# Oxport_Project.net
KiCad netlist of a schematic drawn in EAGLE
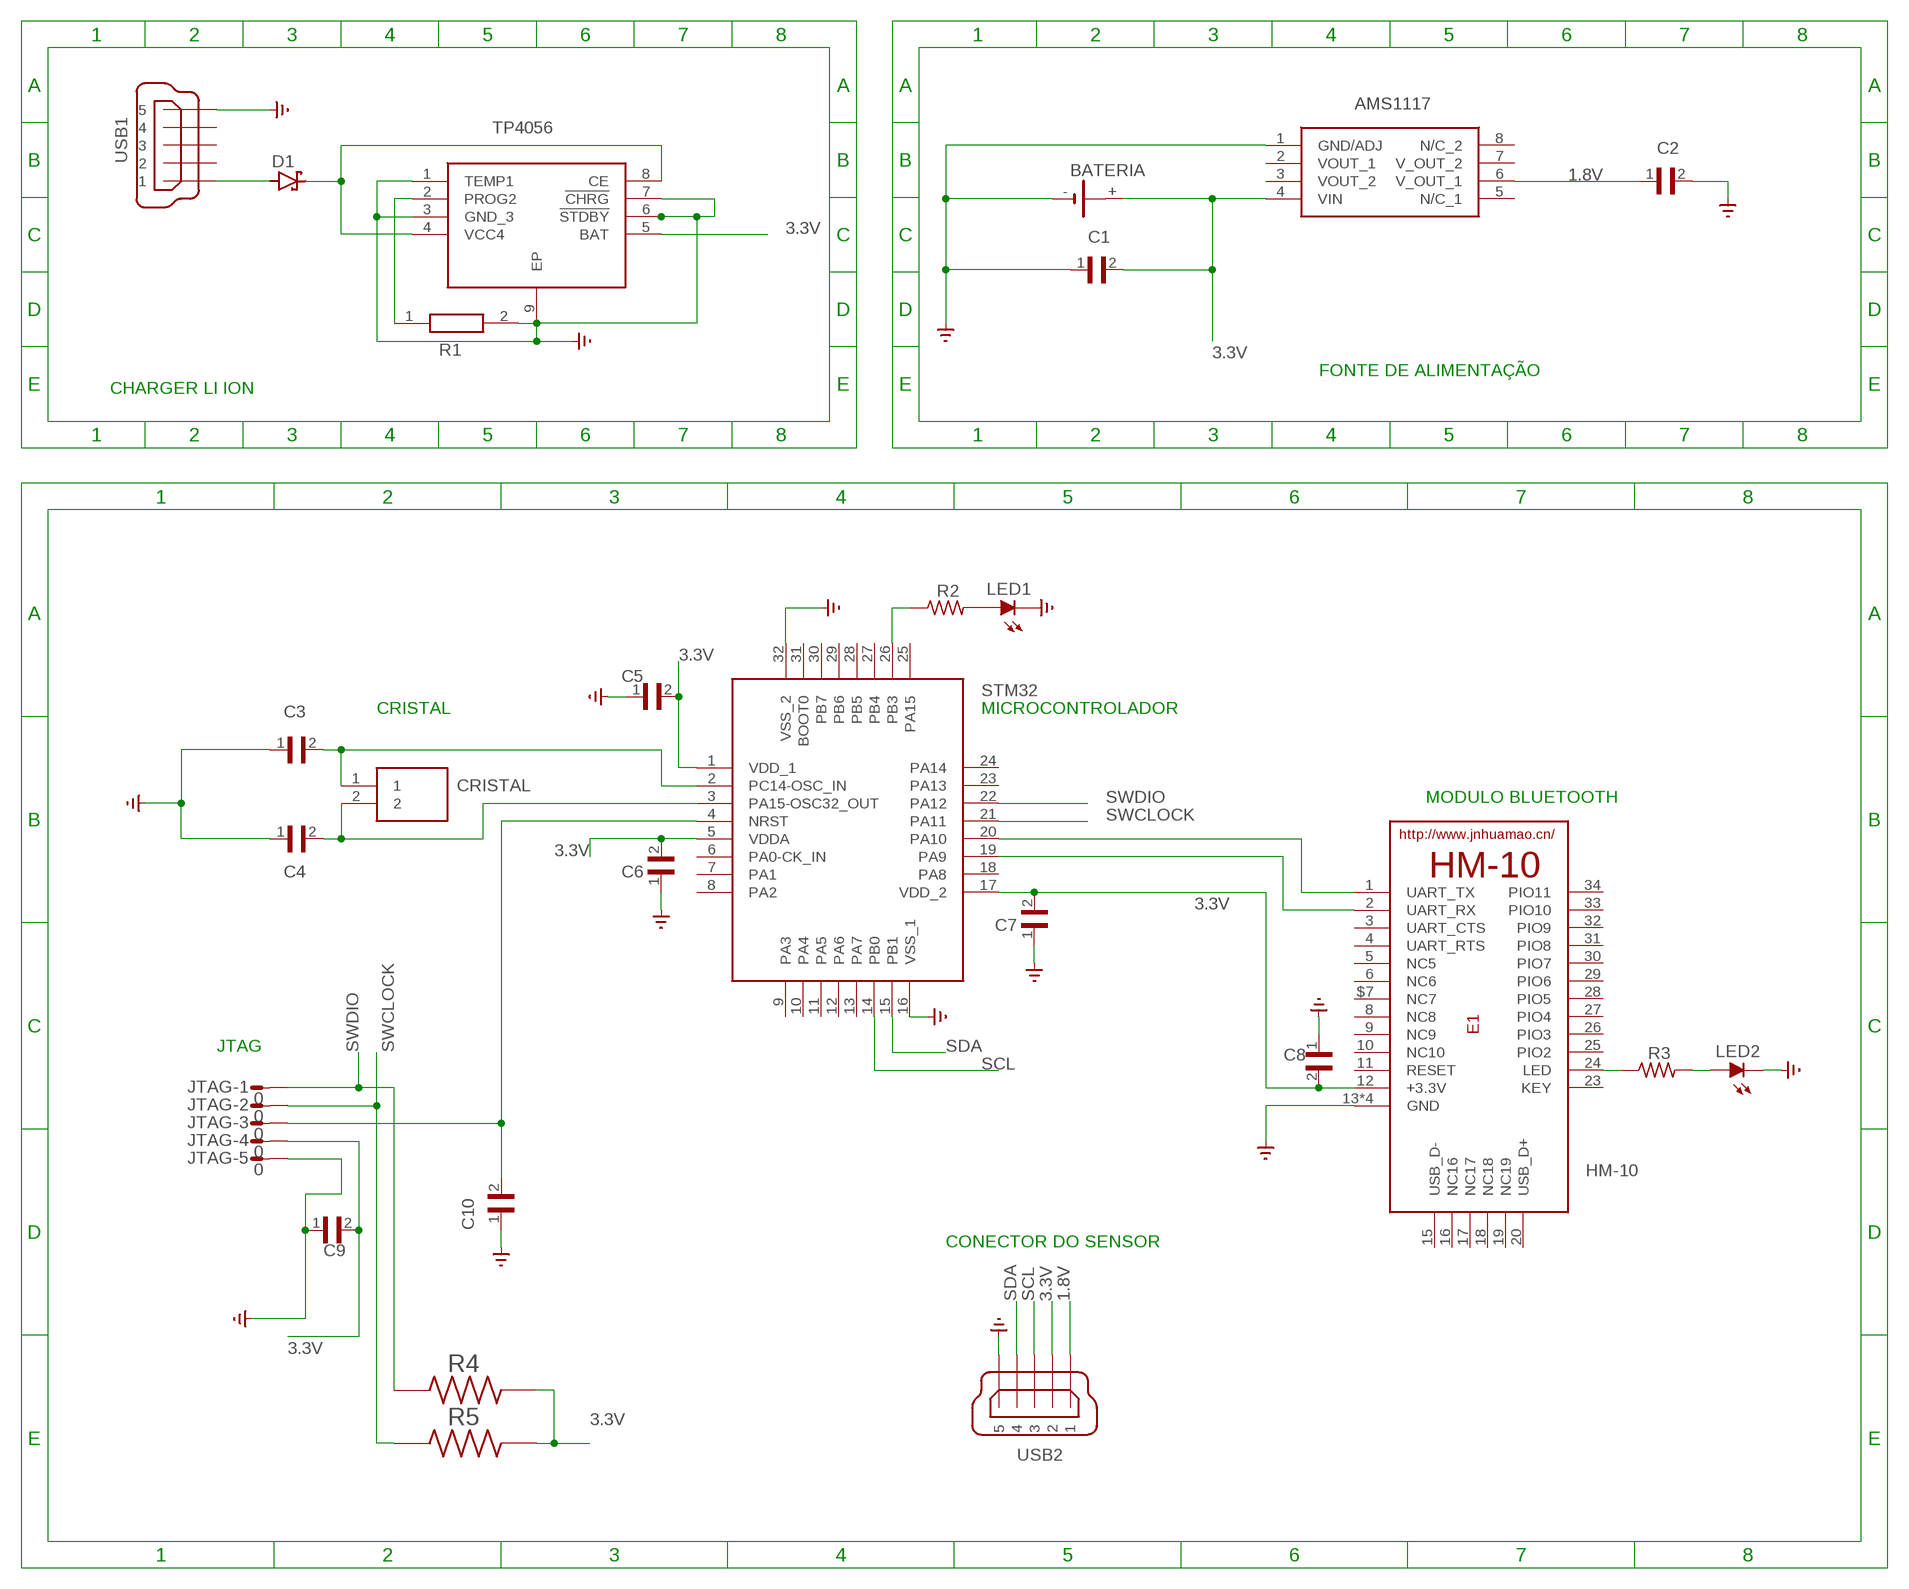
[diagram p0: schematic, sheet 1]

(export (version "E")
  (design (tool "Eeschema 10.0.6"))
  (components
    (comp (ref "3.3V")
      (value "STM32L031K6T6TR")
      (footprint "eagle-import:QFP80P900X900X160-32N")
      (fields (field (name "MOUSER_PART_NUMBER") "511-STM32L031K6T6TR"))
      (libsource (lib "eagle-import") (part "STM32L031K6T6TR"))
    )
    (comp (ref "BATERIA")
      (value "CR1/2")
      (footprint "eagle-import:CR1_2")
      (libsource (lib "eagle-import") (part "CR1/2"))
    )
    (comp (ref "C1")
      (value "VJ0603Y104KLXAC5G")
      (footprint "eagle-import:CAPC1608X92N")
      (fields (field (name "MF") "Vishay"))
      (libsource (lib "eagle-import") (part "VJ0603Y104KLXAC5G"))
    )
    (comp (ref "C2")
      (value "VJ0603Y104KLXAC5G")
      (footprint "eagle-import:CAPC1608X92N")
      (fields (field (name "MF") "Vishay"))
      (libsource (lib "eagle-import") (part "VJ0603Y104KLXAC5G"))
    )
    (comp (ref "C3")
      (value "GRM1885C2A4R3CZ01D")
      (footprint "eagle-import:CAPC1608X90N")
      (fields (field (name "MF") "Murata"))
      (libsource (lib "eagle-import") (part "GRM1885C2A4R3CZ01D"))
    )
    (comp (ref "C4")
      (value "GRM1885C2A4R3CZ01D")
      (footprint "eagle-import:CAPC1608X90N")
      (fields (field (name "MF") "Murata"))
      (libsource (lib "eagle-import") (part "GRM1885C2A4R3CZ01D"))
    )
    (comp (ref "C5")
      (value "VJ0603Y104KLXAC5G")
      (footprint "eagle-import:CAPC1608X92N")
      (fields (field (name "MF") "Vishay"))
      (libsource (lib "eagle-import") (part "VJ0603Y104KLXAC5G"))
    )
    (comp (ref "C6")
      (value "VJ0603Y104KLXAC5G")
      (footprint "eagle-import:CAPC1608X92N")
      (fields (field (name "MF") "Vishay"))
      (libsource (lib "eagle-import") (part "VJ0603Y104KLXAC5G"))
    )
    (comp (ref "C7")
      (value "VJ0603Y104KLXAC5G")
      (footprint "eagle-import:CAPC1608X92N")
      (fields (field (name "MF") "Vishay"))
      (libsource (lib "eagle-import") (part "VJ0603Y104KLXAC5G"))
    )
    (comp (ref "C8")
      (value "VJ0603Y104KLXAC5G")
      (footprint "eagle-import:CAPC1608X92N")
      (fields (field (name "MF") "Vishay"))
      (libsource (lib "eagle-import") (part "VJ0603Y104KLXAC5G"))
    )
    (comp (ref "C9")
      (value "VJ0603Y104KLXAC5G")
      (footprint "eagle-import:CAPC1608X92N")
      (fields (field (name "MF") "Vishay"))
      (libsource (lib "eagle-import") (part "VJ0603Y104KLXAC5G"))
    )
    (comp (ref "C10")
      (value "VJ0603Y104KLXAC5G")
      (footprint "eagle-import:CAPC1608X92N")
      (fields (field (name "MF") "Vishay"))
      (libsource (lib "eagle-import") (part "VJ0603Y104KLXAC5G"))
    )
    (comp (ref "CRISTAL")
      (value "NX3215SA-32.768K-EXS00A-MU0000")
      (footprint "eagle-import:NX3215SA32768KEXS00AMU00003")
      (fields
        (field (name "MANUFACTURER_PART_NUMBER") "NX3215SA-32.768K-EXS00A-MU00003")
        (field (name "MOUSER_PART_NUMBER") "344-NX3215SA32.768K3")
      )
      (libsource (lib "eagle-import") (part "NX3215SA-32.768K-EXS00A-MU0000"))
    )
    (comp (ref "D1")
      (value "BAT60J")
      (footprint "eagle-import:SOD323_ST")
      (libsource (lib "eagle-import") (part "BAT60J"))
    )
    (comp (ref "E1")
      (value "HM-10-BOARD")
      (footprint "eagle-import:26.9X13X2.2_BOARD")
      (libsource (lib "eagle-import") (part "HM-10-BOARD"))
    )
    (comp (ref "IC2")
      (value "AMS1117CS-1.8")
      (footprint "eagle-import:SOIC127P599X175-8N")
      (libsource (lib "eagle-import") (part "AMS1117CS-1.8"))
    )
    (comp (ref "J1")
      (value "TP4056")
      (footprint "eagle-import:SOIC127P600X175-9N")
      (libsource (lib "eagle-import") (part "TP4056"))
    )
    (comp (ref "JTAG")
      (value "0")
      (footprint "eagle-import:L05P")
      (libsource (lib "eagle-import") (part "L05P"))
    )
    (comp (ref "LED1")
      (value "1")
      (footprint "eagle-import:LED_CHIP-LED0603MP")
      (libsource (lib "eagle-import") (part "LED_LEDCHIP-LED0603MP"))
    )
    (comp (ref "LED2")
      (value "1")
      (footprint "eagle-import:LED_CHIP-LED0603MP")
      (libsource (lib "eagle-import") (part "LED_LEDCHIP-LED0603MP"))
    )
    (comp (ref "MINI_USB")
      (value "MINI-USB_SHIELD5P4-32005-501")
      (footprint "eagle-import:32005-501")
      (libsource (lib "eagle-import") (part "MINI-USB_SHIELD5P4-32005-501"))
    )
    (comp (ref "R1")
      (value "CRCW08051K00FKEB")
      (footprint "eagle-import:RESC2012X50N")
      (fields (field (name "MOUSER_PART_NUMBER") "71-CRCW08051K00FKEB"))
      (libsource (lib "eagle-import") (part "CRCW08051K00FKEB"))
    )
    (comp (ref "R2")
      (value "1623232-1")
      (footprint "eagle-import:RESC2012X65N")
      (fields (field (name "MF") "TE Connectivity") (field (name "TOLERANCE") "1%"))
      (libsource (lib "eagle-import") (part "1623232-1"))
    )
    (comp (ref "R3")
      (value "1623232-1")
      (footprint "eagle-import:RESC2012X65N")
      (fields (field (name "MF") "TE Connectivity") (field (name "TOLERANCE") "1%"))
      (libsource (lib "eagle-import") (part "1623232-1"))
    )
    (comp (ref "R4")
      (value "CRGCQ1206J10K")
      (footprint "eagle-import:RESC3115X65N")
      (fields (field (name "COMMENT") "2-2176344-5") (field (name "MF") "TE Connectivity"))
      (libsource (lib "eagle-import") (part "CRGCQ1206J10K"))
    )
    (comp (ref "R5")
      (value "CRGCQ1206J10K")
      (footprint "eagle-import:RESC3115X65N")
      (fields (field (name "COMMENT") "2-2176344-5") (field (name "MF") "TE Connectivity"))
      (libsource (lib "eagle-import") (part "CRGCQ1206J10K"))
    )
    (comp (ref "USB1")
      (value "MINI-USB_SHIELD5P4-32005-501")
      (footprint "eagle-import:32005-501")
      (libsource (lib "eagle-import") (part "MINI-USB_SHIELD5P4-32005-501"))
    )
  )
  (nets
    (net (code "1") (name "/1.8V") (class "Default")
      (node (ref "C2") (pin "1") (pinfunction "1_1") (pintype "passive"))
      (node (ref "IC2") (pin "6") (pinfunction "V_OUT_1_6") (pintype "bidirectional"))
      (node (ref "USB1") (pin "1") (pinfunction "1_1") (pintype "passive"))
    )
    (net (code "2") (name "/3.3V") (class "Default")
      (node (ref "3.3V") (pin "1") (pinfunction "VDD_1_1") (pintype "bidirectional"))
      (node (ref "3.3V") (pin "17") (pinfunction "VDD_2_17") (pintype "bidirectional"))
      (node (ref "3.3V") (pin "5") (pinfunction "VDDA_5") (pintype "bidirectional"))
      (node (ref "BATERIA") (pin "+") (pinfunction "+_+") (pintype "passive"))
      (node (ref "C1") (pin "2") (pinfunction "2_2") (pintype "passive"))
      (node (ref "C5") (pin "2") (pinfunction "2_2") (pintype "passive"))
      (node (ref "C6") (pin "2") (pinfunction "2_2") (pintype "passive"))
      (node (ref "C7") (pin "2") (pinfunction "2_2") (pintype "passive"))
      (node (ref "C8") (pin "2") (pinfunction "2_2") (pintype "passive"))
      (node (ref "C9") (pin "2") (pinfunction "2_2") (pintype "passive"))
      (node (ref "E1") (pin "12") (pinfunction "+3.3V_12") (pintype "bidirectional"))
      (node (ref "IC2") (pin "4") (pinfunction "VIN_4") (pintype "bidirectional"))
      (node (ref "J1") (pin "5") (pinfunction "BAT_5") (pintype "bidirectional"))
      (node (ref "JTAG") (pin "4") (pinfunction "S_4") (pintype "passive"))
      (node (ref "R4") (pin "2") (pinfunction "2_2") (pintype "passive"))
      (node (ref "R5") (pin "2") (pinfunction "2_2") (pintype "passive"))
      (node (ref "USB1") (pin "2") (pinfunction "2_2") (pintype "passive"))
    )
    (net (code "3") (name "/SCL") (class "Default")
      (node (ref "3.3V") (pin "14") (pinfunction "PB0_14") (pintype "bidirectional"))
      (node (ref "USB1") (pin "3") (pinfunction "3_3") (pintype "passive"))
    )
    (net (code "4") (name "/SDA") (class "Default")
      (node (ref "3.3V") (pin "15") (pinfunction "PB1_15") (pintype "bidirectional"))
      (node (ref "USB1") (pin "4") (pinfunction "4_4") (pintype "passive"))
    )
    (net (code "5") (name "/SWCLOCK") (class "Default")
      (node (ref "3.3V") (pin "21") (pinfunction "PA11_21") (pintype "bidirectional"))
      (node (ref "JTAG") (pin "2") (pinfunction "S_2") (pintype "passive"))
      (node (ref "R5") (pin "1") (pinfunction "1_1") (pintype "passive"))
    )
    (net (code "6") (name "/SWDIO") (class "Default")
      (node (ref "3.3V") (pin "22") (pinfunction "PA12_22") (pintype "bidirectional"))
      (node (ref "JTAG") (pin "1") (pinfunction "S_1") (pintype "passive"))
      (node (ref "R4") (pin "1") (pinfunction "1_1") (pintype "passive"))
    )
    (net (code "7") (name "Net-(3.3V-NRST)") (class "Default")
      (node (ref "3.3V") (pin "4") (pinfunction "NRST_4") (pintype "bidirectional"))
      (node (ref "C10") (pin "2") (pinfunction "2_2") (pintype "passive"))
      (node (ref "JTAG") (pin "3") (pinfunction "S_3") (pintype "passive"))
    )
    (net (code "8") (name "Net-(3.3V-PA9)") (class "Default")
      (node (ref "3.3V") (pin "19") (pinfunction "PA9_19") (pintype "bidirectional"))
      (node (ref "E1") (pin "2") (pinfunction "UART_RX_2") (pintype "bidirectional"))
    )
    (net (code "9") (name "Net-(3.3V-PA10)") (class "Default")
      (node (ref "3.3V") (pin "20") (pinfunction "PA10_20") (pintype "bidirectional"))
      (node (ref "E1") (pin "1") (pinfunction "UART_TX_1") (pintype "bidirectional"))
    )
    (net (code "10") (name "Net-(3.3V-PA15-OSC32_OUT)") (class "Default")
      (node (ref "3.3V") (pin "3") (pinfunction "PA15-OSC32_OUT_3") (pintype "bidirectional"))
      (node (ref "C4") (pin "2") (pinfunction "2_2") (pintype "passive"))
      (node (ref "CRISTAL") (pin "2") (pinfunction "2_2") (pintype "bidirectional"))
    )
    (net (code "11") (name "Net-(3.3V-PB3)") (class "Default")
      (node (ref "3.3V") (pin "26") (pinfunction "PB3_26") (pintype "bidirectional"))
      (node (ref "R2") (pin "1") (pinfunction "1_1") (pintype "passive"))
    )
    (net (code "12") (name "Net-(3.3V-PC14-OSC_IN)") (class "Default")
      (node (ref "3.3V") (pin "2") (pinfunction "PC14-OSC_IN_2") (pintype "bidirectional"))
      (node (ref "C3") (pin "2") (pinfunction "2_2") (pintype "passive"))
      (node (ref "CRISTAL") (pin "1") (pinfunction "1_1") (pintype "bidirectional"))
    )
    (net (code "13") (name "Net-(D1-PadA)") (class "Default")
      (node (ref "D1") (pin "A") (pinfunction "A_A") (pintype "passive"))
      (node (ref "MINI_USB") (pin "1") (pinfunction "1_1") (pintype "passive"))
    )
    (net (code "14") (name "Net-(E1-LED)") (class "Default")
      (node (ref "E1") (pin "24") (pinfunction "LED_24") (pintype "bidirectional"))
      (node (ref "R3") (pin "1") (pinfunction "1_1") (pintype "passive"))
    )
    (net (code "15") (name "Net-(J1-CE)") (class "Default")
      (node (ref "D1") (pin "C") (pinfunction "C_C") (pintype "passive"))
      (node (ref "J1") (pin "4") (pinfunction "VCC4_4") (pintype "bidirectional"))
      (node (ref "J1") (pin "8") (pinfunction "CE_8") (pintype "bidirectional"))
    )
    (net (code "16") (name "Net-(J1-PROG2)") (class "Default")
      (node (ref "J1") (pin "2") (pinfunction "PROG2_2") (pintype "bidirectional"))
      (node (ref "R1") (pin "1") (pinfunction "1_1") (pintype "bidirectional"))
    )
    (net (code "17") (name "Net-(LED1-PadA)") (class "Default")
      (node (ref "LED1") (pin "A") (pinfunction "A_A") (pintype "passive"))
      (node (ref "R2") (pin "2") (pinfunction "2_2") (pintype "passive"))
    )
    (net (code "18") (name "Net-(LED2-PadA)") (class "Default")
      (node (ref "LED2") (pin "A") (pinfunction "A_A") (pintype "passive"))
      (node (ref "R3") (pin "2") (pinfunction "2_2") (pintype "passive"))
    )
    (net (code "19") (name "SUPPLY0_GND_") (class "Default")
      (node (ref "3.3V") (pin "16") (pinfunction "VSS_1_16") (pintype "bidirectional"))
      (node (ref "3.3V") (pin "32") (pinfunction "VSS_2_32") (pintype "bidirectional"))
      (node (ref "BATERIA") (pin "-") (pinfunction "-_-") (pintype "passive"))
      (node (ref "C1") (pin "1") (pinfunction "1_1") (pintype "passive"))
      (node (ref "C10") (pin "1") (pinfunction "1_1") (pintype "passive"))
      (node (ref "C2") (pin "2") (pinfunction "2_2") (pintype "passive"))
      (node (ref "C3") (pin "1") (pinfunction "1_1") (pintype "passive"))
      (node (ref "C4") (pin "1") (pinfunction "1_1") (pintype "passive"))
      (node (ref "C5") (pin "1") (pinfunction "1_1") (pintype "passive"))
      (node (ref "C6") (pin "1") (pinfunction "1_1") (pintype "passive"))
      (node (ref "C7") (pin "1") (pinfunction "1_1") (pintype "passive"))
      (node (ref "C8") (pin "1") (pinfunction "1_1") (pintype "passive"))
      (node (ref "C9") (pin "1") (pinfunction "1_1") (pintype "passive"))
      (node (ref "E1") (pin "13") (pinfunction "GND_13") (pintype "bidirectional"))
      (node (ref "E1") (pin "14") (pinfunction "GND_14") (pintype "bidirectional"))
      (node (ref "E1") (pin "21") (pinfunction "GND_21") (pintype "bidirectional"))
      (node (ref "E1") (pin "22") (pinfunction "GND_22") (pintype "bidirectional"))
      (node (ref "IC2") (pin "1") (pinfunction "GND/ADJ_1") (pintype "bidirectional"))
      (node (ref "J1") (pin "1") (pinfunction "TEMP1_1") (pintype "bidirectional"))
      (node (ref "J1") (pin "3") (pinfunction "GND_3_3") (pintype "bidirectional"))
      (node (ref "J1") (pin "6") (pinfunction "~{STDBY}_6") (pintype "bidirectional"))
      (node (ref "J1") (pin "7") (pinfunction "~{CHRG}_7") (pintype "bidirectional"))
      (node (ref "J1") (pin "9") (pinfunction "EP_9") (pintype "bidirectional"))
      (node (ref "JTAG") (pin "5") (pinfunction "S_5") (pintype "passive"))
      (node (ref "LED1") (pin "C") (pinfunction "C_C") (pintype "passive"))
      (node (ref "LED2") (pin "C") (pinfunction "C_C") (pintype "passive"))
      (node (ref "MINI_USB") (pin "5") (pinfunction "5_5") (pintype "passive"))
      (node (ref "R1") (pin "2") (pinfunction "2_2") (pintype "bidirectional"))
      (node (ref "USB1") (pin "5") (pinfunction "5_5") (pintype "passive"))
    )
    (net (code "20") (name "unconnected-(3.3V-BOOT0-Pad31)") (class "Default")
      (node (ref "3.3V") (pin "31") (pinfunction "BOOT0_31") (pintype "bidirectional"))
    )
    (net (code "21") (name "unconnected-(3.3V-PA0-CK_IN-Pad6)") (class "Default")
      (node (ref "3.3V") (pin "6") (pinfunction "PA0-CK_IN_6") (pintype "bidirectional"))
    )
    (net (code "22") (name "unconnected-(3.3V-PA1-Pad7)") (class "Default")
      (node (ref "3.3V") (pin "7") (pinfunction "PA1_7") (pintype "bidirectional"))
    )
    (net (code "23") (name "unconnected-(3.3V-PA2-Pad8)") (class "Default")
      (node (ref "3.3V") (pin "8") (pinfunction "PA2_8") (pintype "bidirectional"))
    )
    (net (code "24") (name "unconnected-(3.3V-PA3-Pad9)") (class "Default")
      (node (ref "3.3V") (pin "9") (pinfunction "PA3_9") (pintype "bidirectional"))
    )
    (net (code "25") (name "unconnected-(3.3V-PA4-Pad10)") (class "Default")
      (node (ref "3.3V") (pin "10") (pinfunction "PA4_10") (pintype "bidirectional"))
    )
    (net (code "26") (name "unconnected-(3.3V-PA5-Pad11)") (class "Default")
      (node (ref "3.3V") (pin "11") (pinfunction "PA5_11") (pintype "bidirectional"))
    )
    (net (code "27") (name "unconnected-(3.3V-PA6-Pad12)") (class "Default")
      (node (ref "3.3V") (pin "12") (pinfunction "PA6_12") (pintype "bidirectional"))
    )
    (net (code "28") (name "unconnected-(3.3V-PA7-Pad13)") (class "Default")
      (node (ref "3.3V") (pin "13") (pinfunction "PA7_13") (pintype "bidirectional"))
    )
    (net (code "29") (name "unconnected-(3.3V-PA8-Pad18)") (class "Default")
      (node (ref "3.3V") (pin "18") (pinfunction "PA8_18") (pintype "bidirectional"))
    )
    (net (code "30") (name "unconnected-(3.3V-PA13-Pad23)") (class "Default")
      (node (ref "3.3V") (pin "23") (pinfunction "PA13_23") (pintype "bidirectional"))
    )
    (net (code "31") (name "unconnected-(3.3V-PA14-Pad24)") (class "Default")
      (node (ref "3.3V") (pin "24") (pinfunction "PA14_24") (pintype "bidirectional"))
    )
    (net (code "32") (name "unconnected-(3.3V-PA15-Pad25)") (class "Default")
      (node (ref "3.3V") (pin "25") (pinfunction "PA15_25") (pintype "bidirectional"))
    )
    (net (code "33") (name "unconnected-(3.3V-PB4-Pad27)") (class "Default")
      (node (ref "3.3V") (pin "27") (pinfunction "PB4_27") (pintype "bidirectional"))
    )
    (net (code "34") (name "unconnected-(3.3V-PB5-Pad28)") (class "Default")
      (node (ref "3.3V") (pin "28") (pinfunction "PB5_28") (pintype "bidirectional"))
    )
    (net (code "35") (name "unconnected-(3.3V-PB6-Pad29)") (class "Default")
      (node (ref "3.3V") (pin "29") (pinfunction "PB6_29") (pintype "bidirectional"))
    )
    (net (code "36") (name "unconnected-(3.3V-PB7-Pad30)") (class "Default")
      (node (ref "3.3V") (pin "30") (pinfunction "PB7_30") (pintype "bidirectional"))
    )
    (net (code "37") (name "unconnected-(BATERIA-+-Pad+@1)") (class "Default")
      (node (ref "BATERIA") (pin "+@1") (pinfunction "+_+@1") (pintype "passive"))
    )
    (net (code "38") (name "unconnected-(E1-KEY-Pad23)") (class "Default")
      (node (ref "E1") (pin "23") (pinfunction "KEY_23") (pintype "bidirectional"))
    )
    (net (code "39") (name "unconnected-(E1-NC5-Pad5)") (class "Default")
      (node (ref "E1") (pin "5") (pinfunction "NC5_5") (pintype "bidirectional"))
    )
    (net (code "40") (name "unconnected-(E1-NC6-Pad6)") (class "Default")
      (node (ref "E1") (pin "6") (pinfunction "NC6_6") (pintype "bidirectional"))
    )
    (net (code "41") (name "unconnected-(E1-NC7-Pad$7)") (class "Default")
      (node (ref "E1") (pin "$7") (pinfunction "NC7_$7") (pintype "bidirectional"))
    )
    (net (code "42") (name "unconnected-(E1-NC8-Pad8)") (class "Default")
      (node (ref "E1") (pin "8") (pinfunction "NC8_8") (pintype "bidirectional"))
    )
    (net (code "43") (name "unconnected-(E1-NC9-Pad9)") (class "Default")
      (node (ref "E1") (pin "9") (pinfunction "NC9_9") (pintype "bidirectional"))
    )
    (net (code "44") (name "unconnected-(E1-NC10-Pad10)") (class "Default")
      (node (ref "E1") (pin "10") (pinfunction "NC10_10") (pintype "bidirectional"))
    )
    (net (code "45") (name "unconnected-(E1-NC16-Pad16)") (class "Default")
      (node (ref "E1") (pin "16") (pinfunction "NC16_16") (pintype "bidirectional"))
    )
    (net (code "46") (name "unconnected-(E1-NC17-Pad17)") (class "Default")
      (node (ref "E1") (pin "17") (pinfunction "NC17_17") (pintype "bidirectional"))
    )
    (net (code "47") (name "unconnected-(E1-NC18-Pad18)") (class "Default")
      (node (ref "E1") (pin "18") (pinfunction "NC18_18") (pintype "bidirectional"))
    )
    (net (code "48") (name "unconnected-(E1-NC19-Pad19)") (class "Default")
      (node (ref "E1") (pin "19") (pinfunction "NC19_19") (pintype "bidirectional"))
    )
    (net (code "49") (name "unconnected-(E1-PIO2-Pad25)") (class "Default")
      (node (ref "E1") (pin "25") (pinfunction "PIO2_25") (pintype "bidirectional"))
    )
    (net (code "50") (name "unconnected-(E1-PIO3-Pad26)") (class "Default")
      (node (ref "E1") (pin "26") (pinfunction "PIO3_26") (pintype "bidirectional"))
    )
    (net (code "51") (name "unconnected-(E1-PIO4-Pad27)") (class "Default")
      (node (ref "E1") (pin "27") (pinfunction "PIO4_27") (pintype "bidirectional"))
    )
    (net (code "52") (name "unconnected-(E1-PIO5-Pad28)") (class "Default")
      (node (ref "E1") (pin "28") (pinfunction "PIO5_28") (pintype "bidirectional"))
    )
    (net (code "53") (name "unconnected-(E1-PIO6-Pad29)") (class "Default")
      (node (ref "E1") (pin "29") (pinfunction "PIO6_29") (pintype "bidirectional"))
    )
    (net (code "54") (name "unconnected-(E1-PIO7-Pad30)") (class "Default")
      (node (ref "E1") (pin "30") (pinfunction "PIO7_30") (pintype "bidirectional"))
    )
    (net (code "55") (name "unconnected-(E1-PIO8-Pad31)") (class "Default")
      (node (ref "E1") (pin "31") (pinfunction "PIO8_31") (pintype "bidirectional"))
    )
    (net (code "56") (name "unconnected-(E1-PIO9-Pad32)") (class "Default")
      (node (ref "E1") (pin "32") (pinfunction "PIO9_32") (pintype "bidirectional"))
    )
    (net (code "57") (name "unconnected-(E1-PIO10-Pad33)") (class "Default")
      (node (ref "E1") (pin "33") (pinfunction "PIO10_33") (pintype "bidirectional"))
    )
    (net (code "58") (name "unconnected-(E1-PIO11-Pad34)") (class "Default")
      (node (ref "E1") (pin "34") (pinfunction "PIO11_34") (pintype "bidirectional"))
    )
    (net (code "59") (name "unconnected-(E1-RESET-Pad11)") (class "Default")
      (node (ref "E1") (pin "11") (pinfunction "RESET_11") (pintype "bidirectional"))
    )
    (net (code "60") (name "unconnected-(E1-UART_CTS-Pad3)") (class "Default")
      (node (ref "E1") (pin "3") (pinfunction "UART_CTS_3") (pintype "bidirectional"))
    )
    (net (code "61") (name "unconnected-(E1-UART_RTS-Pad4)") (class "Default")
      (node (ref "E1") (pin "4") (pinfunction "UART_RTS_4") (pintype "bidirectional"))
    )
    (net (code "62") (name "unconnected-(E1-USB_D+-Pad20)") (class "Default")
      (node (ref "E1") (pin "20") (pinfunction "USB_D+_20") (pintype "bidirectional"))
    )
    (net (code "63") (name "unconnected-(E1-USB_D--Pad15)") (class "Default")
      (node (ref "E1") (pin "15") (pinfunction "USB_D-_15") (pintype "bidirectional"))
    )
    (net (code "64") (name "unconnected-(IC2-N{slash}C_1-Pad5)") (class "Default")
      (node (ref "IC2") (pin "5") (pinfunction "N/C_1_5") (pintype "bidirectional"))
    )
    (net (code "65") (name "unconnected-(IC2-N{slash}C_2-Pad8)") (class "Default")
      (node (ref "IC2") (pin "8") (pinfunction "N/C_2_8") (pintype "bidirectional"))
    )
    (net (code "66") (name "unconnected-(IC2-VOUT_1-Pad2)") (class "Default")
      (node (ref "IC2") (pin "2") (pinfunction "VOUT_1_2") (pintype "bidirectional"))
    )
    (net (code "67") (name "unconnected-(IC2-VOUT_2-Pad3)") (class "Default")
      (node (ref "IC2") (pin "3") (pinfunction "VOUT_2_3") (pintype "bidirectional"))
    )
    (net (code "68") (name "unconnected-(IC2-V_OUT_2-Pad7)") (class "Default")
      (node (ref "IC2") (pin "7") (pinfunction "V_OUT_2_7") (pintype "bidirectional"))
    )
    (net (code "69") (name "unconnected-(MINI_USB-Pad2)") (class "Default")
      (node (ref "MINI_USB") (pin "2") (pinfunction "2_2") (pintype "passive"))
    )
    (net (code "70") (name "unconnected-(MINI_USB-Pad3)") (class "Default")
      (node (ref "MINI_USB") (pin "3") (pinfunction "3_3") (pintype "passive"))
    )
    (net (code "71") (name "unconnected-(MINI_USB-Pad4)") (class "Default")
      (node (ref "MINI_USB") (pin "4") (pinfunction "4_4") (pintype "passive"))
    )
  )
)
